# ledrgbmatrix_arjun_with10mil_clearence.net
KiCad netlist of a schematic drawn in EAGLE
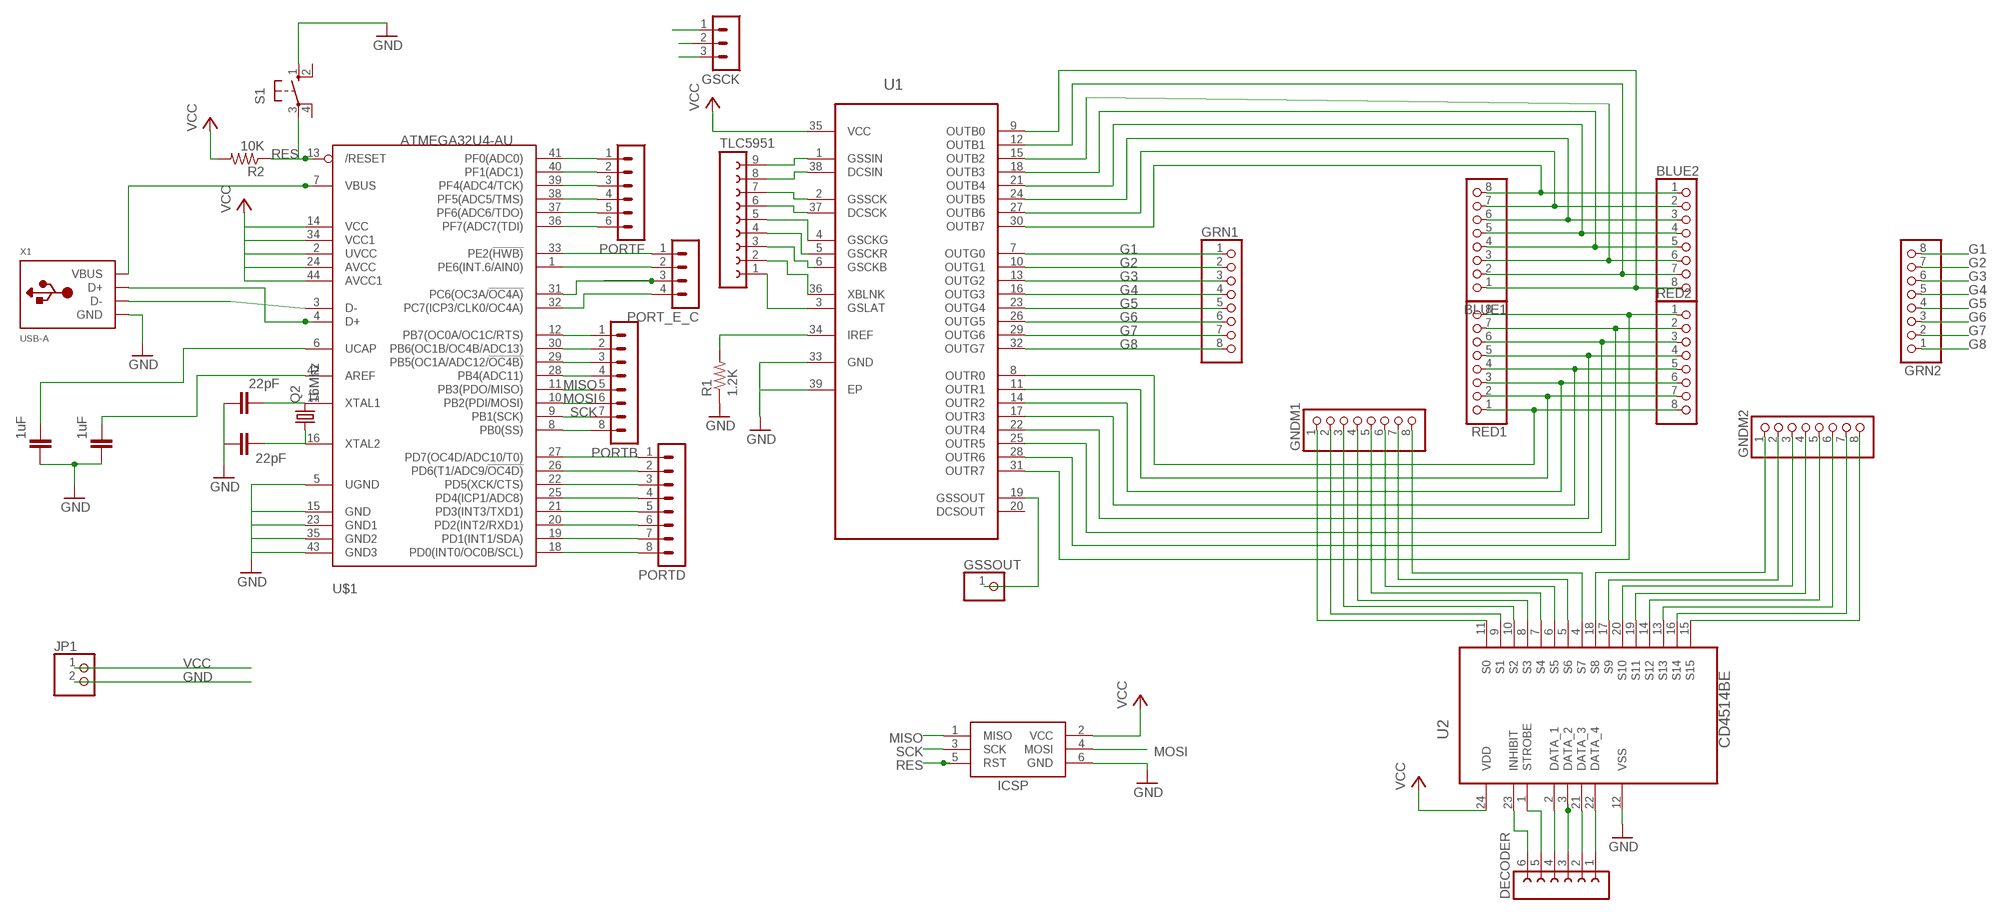
[diagram p0: schematic, sheet 1]

(export (version "E")
  (design (tool "Eeschema 10.0.6"))
  (components
    (comp (ref "BLUE1")
      (value "PINHD-1X8BIG")
      (footprint "eagle-import:1X08-BIG")
      (libsource (lib "eagle-import") (part "PINHD-1X8BIG"))
    )
    (comp (ref "BLUE2")
      (value "PINHD-1X8BIG")
      (footprint "eagle-import:1X08-BIG")
      (libsource (lib "eagle-import") (part "PINHD-1X8BIG"))
    )
    (comp (ref "C1")
      (value "1uF")
      (footprint "eagle-import:C2.5-2")
      (libsource (lib "eagle-import") (part "C2.5/2"))
    )
    (comp (ref "C2")
      (value "1uF")
      (footprint "eagle-import:C2.5-2")
      (libsource (lib "eagle-import") (part "C2.5/2"))
    )
    (comp (ref "C3")
      (value "22pF")
      (footprint "eagle-import:C2.5-2")
      (libsource (lib "eagle-import") (part "C2.5/2"))
    )
    (comp (ref "C4")
      (value "22pF")
      (footprint "eagle-import:C2.5-2")
      (libsource (lib "eagle-import") (part "C2.5/2"))
    )
    (comp (ref "DECODER")
      (value "FE06-1")
      (footprint "eagle-import:FE06")
      (libsource (lib "eagle-import") (part "FE06-1"))
    )
    (comp (ref "GNDM1")
      (value "PINHD-1X8BIG")
      (footprint "eagle-import:1X08-BIG")
      (libsource (lib "eagle-import") (part "PINHD-1X8BIG"))
    )
    (comp (ref "GNDM2")
      (value "PINHD-1X8BIG")
      (footprint "eagle-import:1X08-BIG")
      (libsource (lib "eagle-import") (part "PINHD-1X8BIG"))
    )
    (comp (ref "GRN1")
      (value "PINHD-1X8BIG")
      (footprint "eagle-import:1X08-BIG")
      (libsource (lib "eagle-import") (part "PINHD-1X8BIG"))
    )
    (comp (ref "GRN2")
      (value "PINHD-1X8BIG")
      (footprint "eagle-import:1X08-BIG")
      (libsource (lib "eagle-import") (part "PINHD-1X8BIG"))
    )
    (comp (ref "GSCK")
      (value "MA03-1")
      (footprint "eagle-import:MA03-1")
      (libsource (lib "eagle-import") (part "MA03-1"))
    )
    (comp (ref "GSSOUT")
      (value "PINHD-1X1")
      (footprint "eagle-import:1X01")
      (libsource (lib "eagle-import") (part "PINHD-1X1"))
    )
    (comp (ref "ICSP")
      (value "AVRISP-6")
      (footprint "eagle-import:AVRISP")
      (libsource (lib "eagle-import") (part "AVRISP-6"))
    )
    (comp (ref "JP1")
      (value "PINHD-1X2")
      (footprint "eagle-import:1X02")
      (libsource (lib "eagle-import") (part "PINHD-1X2"))
    )
    (comp (ref "PORTB")
      (value "MA08-1")
      (footprint "eagle-import:MA08-1")
      (libsource (lib "eagle-import") (part "MA08-1"))
    )
    (comp (ref "PORTD")
      (value "MA08-1")
      (footprint "eagle-import:MA08-1")
      (libsource (lib "eagle-import") (part "MA08-1"))
    )
    (comp (ref "PORTF")
      (value "MA06-1")
      (footprint "eagle-import:MA06-1")
      (libsource (lib "eagle-import") (part "MA06-1"))
    )
    (comp (ref "PORT_E_C")
      (value "MA04-1")
      (footprint "eagle-import:MA04-1")
      (libsource (lib "eagle-import") (part "MA04-1"))
    )
    (comp (ref "Q2")
      (value "16Mhz")
      (footprint "eagle-import:HC49U-V")
      (libsource (lib "eagle-import") (part "CRYSTALHC49U-V"))
    )
    (comp (ref "R1")
      (value "1.2K")
      (footprint "eagle-import:0207_12")
      (libsource (lib "eagle-import") (part "R-US_0207/12"))
    )
    (comp (ref "R2")
      (value "10K")
      (footprint "eagle-import:0207_12")
      (libsource (lib "eagle-import") (part "R-US_0207/12"))
    )
    (comp (ref "RED1")
      (value "PINHD-1X8BIG")
      (footprint "eagle-import:1X08-BIG")
      (libsource (lib "eagle-import") (part "PINHD-1X8BIG"))
    )
    (comp (ref "RED2")
      (value "PINHD-1X8BIG")
      (footprint "eagle-import:1X08-BIG")
      (libsource (lib "eagle-import") (part "PINHD-1X8BIG"))
    )
    (comp (ref "S1")
      (value "10-XX")
      (footprint "eagle-import:B3F-10XX")
      (fields (field (name "MPN") "B3F-1000"))
      (libsource (lib "eagle-import") (part "10-XX"))
    )
    (comp (ref "TLC5951")
      (value "FE09-1")
      (footprint "eagle-import:FE09")
      (libsource (lib "eagle-import") (part "FE09-1"))
    )
    (comp (ref "U$1")
      (value "ATMEGA32U4-AU")
      (footprint "eagle-import:TQFP44")
      (libsource (lib "eagle-import") (part "ATMEGA32U4-AU"))
    )
    (comp (ref "U1")
      (value "TLC5951DAP")
      (footprint "eagle-import:SOP65P810X120-39N")
      (libsource (lib "eagle-import") (part "TLC5951DAP"))
    )
    (comp (ref "U2")
      (value "CD4514BE")
      (footprint "eagle-import:DIP254P1080X508-24")
      (libsource (lib "eagle-import") (part "CD4514BE"))
    )
    (comp (ref "X1")
      (value "USB-A")
      (footprint "eagle-import:MOLEX_480371000")
      (libsource (lib "eagle-import") (part "USB-A"))
    )
  )
  (nets
    (net (code "1") (name "/G1") (class "Default")
      (node (ref "GRN1") (pin "1") (pinfunction "1_1") (pintype "passive"))
      (node (ref "GRN2") (pin "8") (pinfunction "8_8") (pintype "passive"))
      (node (ref "U1") (pin "7") (pinfunction "OUTG0_7") (pintype "output"))
    )
    (net (code "2") (name "/G2") (class "Default")
      (node (ref "GRN1") (pin "2") (pinfunction "2_2") (pintype "passive"))
      (node (ref "GRN2") (pin "7") (pinfunction "7_7") (pintype "passive"))
      (node (ref "U1") (pin "10") (pinfunction "OUTG1_10") (pintype "output"))
    )
    (net (code "3") (name "/G3") (class "Default")
      (node (ref "GRN1") (pin "3") (pinfunction "3_3") (pintype "passive"))
      (node (ref "GRN2") (pin "6") (pinfunction "6_6") (pintype "passive"))
      (node (ref "U1") (pin "13") (pinfunction "OUTG2_13") (pintype "output"))
    )
    (net (code "4") (name "/G4") (class "Default")
      (node (ref "GRN1") (pin "4") (pinfunction "4_4") (pintype "passive"))
      (node (ref "GRN2") (pin "5") (pinfunction "5_5") (pintype "passive"))
      (node (ref "U1") (pin "16") (pinfunction "OUTG3_16") (pintype "output"))
    )
    (net (code "5") (name "/G5") (class "Default")
      (node (ref "GRN1") (pin "5") (pinfunction "5_5") (pintype "passive"))
      (node (ref "GRN2") (pin "4") (pinfunction "4_4") (pintype "passive"))
      (node (ref "U1") (pin "23") (pinfunction "OUTG4_23") (pintype "output"))
    )
    (net (code "6") (name "/G6") (class "Default")
      (node (ref "GRN1") (pin "6") (pinfunction "6_6") (pintype "passive"))
      (node (ref "GRN2") (pin "3") (pinfunction "3_3") (pintype "passive"))
      (node (ref "U1") (pin "26") (pinfunction "OUTG5_26") (pintype "output"))
    )
    (net (code "7") (name "/G7") (class "Default")
      (node (ref "GRN1") (pin "7") (pinfunction "7_7") (pintype "passive"))
      (node (ref "GRN2") (pin "2") (pinfunction "2_2") (pintype "passive"))
      (node (ref "U1") (pin "29") (pinfunction "OUTG6_29") (pintype "output"))
    )
    (net (code "8") (name "/G8") (class "Default")
      (node (ref "GRN1") (pin "8") (pinfunction "8_8") (pintype "passive"))
      (node (ref "GRN2") (pin "1") (pinfunction "1_1") (pintype "passive"))
      (node (ref "U1") (pin "32") (pinfunction "OUTG7_32") (pintype "output"))
    )
    (net (code "9") (name "/GSSCK") (class "Default")
      (node (ref "GSCK") (pin "2") (pinfunction "2_2") (pintype "passive"))
      (node (ref "TLC5951") (pin "7") (pinfunction "7_7") (pintype "passive"))
      (node (ref "U1") (pin "2") (pinfunction "GSSCK_2") (pintype "input"))
    )
    (net (code "10") (name "/MISO") (class "Default")
      (node (ref "ICSP") (pin "1") (pinfunction "MISO_1") (pintype "input"))
      (node (ref "PORTB") (pin "5") (pinfunction "5_5") (pintype "passive"))
      (node (ref "U$1") (pin "11") (pinfunction "PB3(PDO/MISO)_11") (pintype "bidirectional"))
    )
    (net (code "11") (name "/MOSI") (class "Default")
      (node (ref "ICSP") (pin "4") (pinfunction "MOSI_4") (pintype "output"))
      (node (ref "PORTB") (pin "6") (pinfunction "6_6") (pintype "passive"))
      (node (ref "U$1") (pin "10") (pinfunction "PB2(PDI/MOSI)_10") (pintype "bidirectional"))
    )
    (net (code "12") (name "/RES") (class "Default")
      (node (ref "ICSP") (pin "5") (pinfunction "RST_5") (pintype "output"))
      (node (ref "R2") (pin "1") (pinfunction "1_1") (pintype "passive"))
      (node (ref "S1") (pin "3") (pinfunction "P_3") (pintype "passive"))
      (node (ref "U$1") (pin "13") (pinfunction "/RESET_13") (pintype "bidirectional"))
    )
    (net (code "13") (name "/SCK") (class "Default")
      (node (ref "ICSP") (pin "3") (pinfunction "SCK_3") (pintype "output"))
      (node (ref "PORTB") (pin "7") (pinfunction "7_7") (pintype "passive"))
      (node (ref "U$1") (pin "9") (pinfunction "PB1(SCK)_9") (pintype "bidirectional"))
    )
    (net (code "14") (name "GND") (class "Default")
      (node (ref "C1") (pin "1") (pinfunction "1_1") (pintype "passive"))
      (node (ref "C2") (pin "1") (pinfunction "1_1") (pintype "passive"))
      (node (ref "C3") (pin "1") (pinfunction "1_1") (pintype "passive"))
      (node (ref "C4") (pin "1") (pinfunction "1_1") (pintype "passive"))
      (node (ref "ICSP") (pin "6") (pinfunction "GND_6") (pintype "power_in"))
      (node (ref "JP1") (pin "2") (pinfunction "2_2") (pintype "passive"))
      (node (ref "R1") (pin "1") (pinfunction "1_1") (pintype "passive"))
      (node (ref "S1") (pin "1") (pinfunction "S_1") (pintype "passive"))
      (node (ref "U$1") (pin "15") (pinfunction "GND_15") (pintype "bidirectional"))
      (node (ref "U$1") (pin "23") (pinfunction "GND1_23") (pintype "bidirectional"))
      (node (ref "U$1") (pin "35") (pinfunction "GND2_35") (pintype "bidirectional"))
      (node (ref "U$1") (pin "43") (pinfunction "GND3_43") (pintype "bidirectional"))
      (node (ref "U$1") (pin "5") (pinfunction "UGND_5") (pintype "bidirectional"))
      (node (ref "U1") (pin "33") (pinfunction "GND_33") (pintype "passive"))
      (node (ref "U1") (pin "39") (pinfunction "EP_39") (pintype "passive"))
      (node (ref "U2") (pin "12") (pinfunction "VSS_12") (pintype "power_in"))
      (node (ref "X1") (pin "4") (pinfunction "GND_4") (pintype "power_in"))
    )
    (net (code "15") (name "Net-(U$1-AREF)") (class "Default")
      (node (ref "C1") (pin "2") (pinfunction "2_2") (pintype "passive"))
      (node (ref "U$1") (pin "42") (pinfunction "AREF_42") (pintype "bidirectional"))
    )
    (net (code "16") (name "Net-(U$1-D+)") (class "Default")
      (node (ref "U$1") (pin "4") (pinfunction "D+_4") (pintype "bidirectional"))
      (node (ref "X1") (pin "3") (pinfunction "D+_3") (pintype "bidirectional"))
    )
    (net (code "17") (name "Net-(U$1-D-)") (class "Default")
      (node (ref "U$1") (pin "3") (pinfunction "D-_3") (pintype "bidirectional"))
      (node (ref "X1") (pin "2") (pinfunction "D-_2") (pintype "bidirectional"))
    )
    (net (code "18") (name "Net-(U$1-PB0(SS))") (class "Default")
      (node (ref "PORTB") (pin "8") (pinfunction "8_8") (pintype "passive"))
      (node (ref "U$1") (pin "8") (pinfunction "PB0(SS)_8") (pintype "bidirectional"))
    )
    (net (code "19") (name "Net-(U$1-PB4(ADC11))") (class "Default")
      (node (ref "PORTB") (pin "4") (pinfunction "4_4") (pintype "passive"))
      (node (ref "U$1") (pin "28") (pinfunction "PB4(ADC11)_28") (pintype "bidirectional"))
    )
    (net (code "20") (name "Net-(U$1-PB5(OC1A{slash}ADC12{slash}~{OC4B}))") (class "Default")
      (node (ref "PORTB") (pin "3") (pinfunction "3_3") (pintype "passive"))
      (node (ref "U$1") (pin "29") (pinfunction "PB5(OC1A/ADC12/~{OC4B})_29") (pintype "bidirectional"))
    )
    (net (code "21") (name "Net-(U$1-PB6(OC1B{slash}OC4B{slash}ADC13))") (class "Default")
      (node (ref "PORTB") (pin "2") (pinfunction "2_2") (pintype "passive"))
      (node (ref "U$1") (pin "30") (pinfunction "PB6(OC1B/OC4B/ADC13)_30") (pintype "bidirectional"))
    )
    (net (code "22") (name "Net-(U$1-PB7(OC0A{slash}OC1C{slash}RTS))") (class "Default")
      (node (ref "PORTB") (pin "1") (pinfunction "1_1") (pintype "passive"))
      (node (ref "U$1") (pin "12") (pinfunction "PB7(OC0A/OC1C/RTS)_12") (pintype "bidirectional"))
    )
    (net (code "23") (name "Net-(U$1-PC6(OC3A{slash}~{OC4A}))") (class "Default")
      (node (ref "PORT_E_C") (pin "3") (pinfunction "3_3") (pintype "passive"))
      (node (ref "U$1") (pin "31") (pinfunction "PC6(OC3A/~{OC4A})_31") (pintype "bidirectional"))
    )
    (net (code "24") (name "Net-(U$1-PC7(ICP3{slash}CLK0{slash}OC4A))") (class "Default")
      (node (ref "PORT_E_C") (pin "4") (pinfunction "4_4") (pintype "passive"))
      (node (ref "U$1") (pin "32") (pinfunction "PC7(ICP3/CLK0/OC4A)_32") (pintype "bidirectional"))
    )
    (net (code "25") (name "Net-(U$1-PD0(INT0{slash}OC0B{slash}SCL))") (class "Default")
      (node (ref "PORTD") (pin "8") (pinfunction "8_8") (pintype "passive"))
      (node (ref "U$1") (pin "18") (pinfunction "PD0(INT0/OC0B/SCL)_18") (pintype "bidirectional"))
    )
    (net (code "26") (name "Net-(U$1-PD1(INT1{slash}SDA))") (class "Default")
      (node (ref "PORTD") (pin "7") (pinfunction "7_7") (pintype "passive"))
      (node (ref "U$1") (pin "19") (pinfunction "PD1(INT1/SDA)_19") (pintype "bidirectional"))
    )
    (net (code "27") (name "Net-(U$1-PD2(INT2{slash}RXD1))") (class "Default")
      (node (ref "PORTD") (pin "6") (pinfunction "6_6") (pintype "passive"))
      (node (ref "U$1") (pin "20") (pinfunction "PD2(INT2/RXD1)_20") (pintype "bidirectional"))
    )
    (net (code "28") (name "Net-(U$1-PD3(INT3{slash}TXD1))") (class "Default")
      (node (ref "PORTD") (pin "5") (pinfunction "5_5") (pintype "passive"))
      (node (ref "U$1") (pin "21") (pinfunction "PD3(INT3/TXD1)_21") (pintype "bidirectional"))
    )
    (net (code "29") (name "Net-(U$1-PD4(ICP1{slash}ADC8))") (class "Default")
      (node (ref "PORTD") (pin "4") (pinfunction "4_4") (pintype "passive"))
      (node (ref "U$1") (pin "25") (pinfunction "PD4(ICP1/ADC8)_25") (pintype "bidirectional"))
    )
    (net (code "30") (name "Net-(U$1-PD5(XCK{slash}CTS))") (class "Default")
      (node (ref "PORTD") (pin "3") (pinfunction "3_3") (pintype "passive"))
      (node (ref "U$1") (pin "22") (pinfunction "PD5(XCK/CTS)_22") (pintype "bidirectional"))
    )
    (net (code "31") (name "Net-(U$1-PD6(T1{slash}ADC9{slash}~{OC4D}))") (class "Default")
      (node (ref "PORTD") (pin "2") (pinfunction "2_2") (pintype "passive"))
      (node (ref "U$1") (pin "26") (pinfunction "PD6(T1/ADC9/~{OC4D})_26") (pintype "bidirectional"))
    )
    (net (code "32") (name "Net-(U$1-PD7(OC4D{slash}ADC10{slash}T0))") (class "Default")
      (node (ref "PORTD") (pin "1") (pinfunction "1_1") (pintype "passive"))
      (node (ref "U$1") (pin "27") (pinfunction "PD7(OC4D/ADC10/T0)_27") (pintype "bidirectional"))
    )
    (net (code "33") (name "Net-(U$1-PE2(~{HWB}))") (class "Default")
      (node (ref "PORT_E_C") (pin "1") (pinfunction "1_1") (pintype "passive"))
      (node (ref "U$1") (pin "33") (pinfunction "PE2(~{HWB})_33") (pintype "bidirectional"))
    )
    (net (code "34") (name "Net-(U$1-PE6(INT.6{slash}AIN0))") (class "Default")
      (node (ref "PORT_E_C") (pin "2") (pinfunction "2_2") (pintype "passive"))
      (node (ref "U$1") (pin "1") (pinfunction "PE6(INT.6/AIN0)_1") (pintype "bidirectional"))
    )
    (net (code "35") (name "Net-(U$1-PF0(ADC0))") (class "Default")
      (node (ref "PORTF") (pin "1") (pinfunction "1_1") (pintype "passive"))
      (node (ref "U$1") (pin "41") (pinfunction "PF0(ADC0)_41") (pintype "bidirectional"))
    )
    (net (code "36") (name "Net-(U$1-PF1(ADC1))") (class "Default")
      (node (ref "PORTF") (pin "2") (pinfunction "2_2") (pintype "passive"))
      (node (ref "U$1") (pin "40") (pinfunction "PF1(ADC1)_40") (pintype "bidirectional"))
    )
    (net (code "37") (name "Net-(U$1-PF4(ADC4{slash}TCK))") (class "Default")
      (node (ref "PORTF") (pin "3") (pinfunction "3_3") (pintype "passive"))
      (node (ref "U$1") (pin "39") (pinfunction "PF4(ADC4/TCK)_39") (pintype "bidirectional"))
    )
    (net (code "38") (name "Net-(U$1-PF5(ADC5{slash}TMS))") (class "Default")
      (node (ref "PORTF") (pin "4") (pinfunction "4_4") (pintype "passive"))
      (node (ref "U$1") (pin "38") (pinfunction "PF5(ADC5/TMS)_38") (pintype "bidirectional"))
    )
    (net (code "39") (name "Net-(U$1-PF6(ADC6{slash}TDO))") (class "Default")
      (node (ref "PORTF") (pin "5") (pinfunction "5_5") (pintype "passive"))
      (node (ref "U$1") (pin "37") (pinfunction "PF6(ADC6/TDO)_37") (pintype "bidirectional"))
    )
    (net (code "40") (name "Net-(U$1-PF7(ADC7(TDI))") (class "Default")
      (node (ref "PORTF") (pin "6") (pinfunction "6_6") (pintype "passive"))
      (node (ref "U$1") (pin "36") (pinfunction "PF7(ADC7(TDI)_36") (pintype "bidirectional"))
    )
    (net (code "41") (name "Net-(U$1-UCAP)") (class "Default")
      (node (ref "C2") (pin "2") (pinfunction "2_2") (pintype "passive"))
      (node (ref "U$1") (pin "6") (pinfunction "UCAP_6") (pintype "bidirectional"))
    )
    (net (code "42") (name "Net-(U$1-VBUS)") (class "Default")
      (node (ref "U$1") (pin "7") (pinfunction "VBUS_7") (pintype "bidirectional"))
      (node (ref "X1") (pin "1") (pinfunction "VBUS_1") (pintype "power_in"))
    )
    (net (code "43") (name "Net-(U$1-XTAL1)") (class "Default")
      (node (ref "C3") (pin "2") (pinfunction "2_2") (pintype "passive"))
      (node (ref "Q2") (pin "2") (pinfunction "2_2") (pintype "passive"))
      (node (ref "U$1") (pin "17") (pinfunction "XTAL1_17") (pintype "bidirectional"))
    )
    (net (code "44") (name "Net-(U$1-XTAL2)") (class "Default")
      (node (ref "C4") (pin "2") (pinfunction "2_2") (pintype "passive"))
      (node (ref "Q2") (pin "1") (pinfunction "1_1") (pintype "passive"))
      (node (ref "U$1") (pin "16") (pinfunction "XTAL2_16") (pintype "bidirectional"))
    )
    (net (code "45") (name "Net-(U1-DCSCK)") (class "Default")
      (node (ref "TLC5951") (pin "6") (pinfunction "6_6") (pintype "passive"))
      (node (ref "U1") (pin "37") (pinfunction "DCSCK_37") (pintype "input"))
    )
    (net (code "46") (name "Net-(U1-DCSIN)") (class "Default")
      (node (ref "TLC5951") (pin "8") (pinfunction "8_8") (pintype "passive"))
      (node (ref "U1") (pin "38") (pinfunction "DCSIN_38") (pintype "input"))
    )
    (net (code "47") (name "Net-(U1-GSCKB)") (class "Default")
      (node (ref "TLC5951") (pin "3") (pinfunction "3_3") (pintype "passive"))
      (node (ref "U1") (pin "6") (pinfunction "GSCKB_6") (pintype "input"))
    )
    (net (code "48") (name "Net-(U1-GSCKG)") (class "Default")
      (node (ref "TLC5951") (pin "5") (pinfunction "5_5") (pintype "passive"))
      (node (ref "U1") (pin "4") (pinfunction "GSCKG_4") (pintype "input"))
    )
    (net (code "49") (name "Net-(U1-GSCKR)") (class "Default")
      (node (ref "TLC5951") (pin "4") (pinfunction "4_4") (pintype "passive"))
      (node (ref "U1") (pin "5") (pinfunction "GSCKR_5") (pintype "input"))
    )
    (net (code "50") (name "Net-(U1-GSLAT)") (class "Default")
      (node (ref "TLC5951") (pin "1") (pinfunction "1_1") (pintype "passive"))
      (node (ref "U1") (pin "3") (pinfunction "GSLAT_3") (pintype "input"))
    )
    (net (code "51") (name "Net-(U1-GSSIN)") (class "Default")
      (node (ref "TLC5951") (pin "9") (pinfunction "9_9") (pintype "passive"))
      (node (ref "U1") (pin "1") (pinfunction "GSSIN_1") (pintype "input"))
    )
    (net (code "52") (name "Net-(U1-GSSOUT)") (class "Default")
      (node (ref "GSSOUT") (pin "1") (pinfunction "1_1") (pintype "passive"))
      (node (ref "U1") (pin "19") (pinfunction "GSSOUT_19") (pintype "output"))
    )
    (net (code "53") (name "Net-(U1-IREF)") (class "Default")
      (node (ref "R1") (pin "2") (pinfunction "2_2") (pintype "passive"))
      (node (ref "U1") (pin "34") (pinfunction "IREF_34") (pintype "bidirectional"))
    )
    (net (code "54") (name "Net-(U1-OUTB0)") (class "Default")
      (node (ref "BLUE1") (pin "1") (pinfunction "1_1") (pintype "passive"))
      (node (ref "BLUE2") (pin "8") (pinfunction "8_8") (pintype "passive"))
      (node (ref "U1") (pin "9") (pinfunction "OUTB0_9") (pintype "output"))
    )
    (net (code "55") (name "Net-(U1-OUTB1)") (class "Default")
      (node (ref "BLUE1") (pin "2") (pinfunction "2_2") (pintype "passive"))
      (node (ref "BLUE2") (pin "7") (pinfunction "7_7") (pintype "passive"))
      (node (ref "U1") (pin "12") (pinfunction "OUTB1_12") (pintype "output"))
    )
    (net (code "56") (name "Net-(U1-OUTB2)") (class "Default")
      (node (ref "BLUE1") (pin "3") (pinfunction "3_3") (pintype "passive"))
      (node (ref "BLUE2") (pin "6") (pinfunction "6_6") (pintype "passive"))
      (node (ref "U1") (pin "15") (pinfunction "OUTB2_15") (pintype "output"))
    )
    (net (code "57") (name "Net-(U1-OUTB3)") (class "Default")
      (node (ref "BLUE1") (pin "4") (pinfunction "4_4") (pintype "passive"))
      (node (ref "BLUE2") (pin "5") (pinfunction "5_5") (pintype "passive"))
      (node (ref "U1") (pin "18") (pinfunction "OUTB3_18") (pintype "output"))
    )
    (net (code "58") (name "Net-(U1-OUTB4)") (class "Default")
      (node (ref "BLUE1") (pin "5") (pinfunction "5_5") (pintype "passive"))
      (node (ref "BLUE2") (pin "4") (pinfunction "4_4") (pintype "passive"))
      (node (ref "U1") (pin "21") (pinfunction "OUTB4_21") (pintype "output"))
    )
    (net (code "59") (name "Net-(U1-OUTB5)") (class "Default")
      (node (ref "BLUE1") (pin "6") (pinfunction "6_6") (pintype "passive"))
      (node (ref "BLUE2") (pin "3") (pinfunction "3_3") (pintype "passive"))
      (node (ref "U1") (pin "24") (pinfunction "OUTB5_24") (pintype "output"))
    )
    (net (code "60") (name "Net-(U1-OUTB6)") (class "Default")
      (node (ref "BLUE1") (pin "7") (pinfunction "7_7") (pintype "passive"))
      (node (ref "BLUE2") (pin "2") (pinfunction "2_2") (pintype "passive"))
      (node (ref "U1") (pin "27") (pinfunction "OUTB6_27") (pintype "output"))
    )
    (net (code "61") (name "Net-(U1-OUTB7)") (class "Default")
      (node (ref "BLUE1") (pin "8") (pinfunction "8_8") (pintype "passive"))
      (node (ref "BLUE2") (pin "1") (pinfunction "1_1") (pintype "passive"))
      (node (ref "U1") (pin "30") (pinfunction "OUTB7_30") (pintype "output"))
    )
    (net (code "62") (name "Net-(U1-OUTR0)") (class "Default")
      (node (ref "RED1") (pin "1") (pinfunction "1_1") (pintype "passive"))
      (node (ref "RED2") (pin "8") (pinfunction "8_8") (pintype "passive"))
      (node (ref "U1") (pin "8") (pinfunction "OUTR0_8") (pintype "output"))
    )
    (net (code "63") (name "Net-(U1-OUTR1)") (class "Default")
      (node (ref "RED1") (pin "2") (pinfunction "2_2") (pintype "passive"))
      (node (ref "RED2") (pin "7") (pinfunction "7_7") (pintype "passive"))
      (node (ref "U1") (pin "11") (pinfunction "OUTR1_11") (pintype "output"))
    )
    (net (code "64") (name "Net-(U1-OUTR2)") (class "Default")
      (node (ref "RED1") (pin "3") (pinfunction "3_3") (pintype "passive"))
      (node (ref "RED2") (pin "6") (pinfunction "6_6") (pintype "passive"))
      (node (ref "U1") (pin "14") (pinfunction "OUTR2_14") (pintype "output"))
    )
    (net (code "65") (name "Net-(U1-OUTR3)") (class "Default")
      (node (ref "RED1") (pin "4") (pinfunction "4_4") (pintype "passive"))
      (node (ref "RED2") (pin "5") (pinfunction "5_5") (pintype "passive"))
      (node (ref "U1") (pin "17") (pinfunction "OUTR3_17") (pintype "output"))
    )
    (net (code "66") (name "Net-(U1-OUTR4)") (class "Default")
      (node (ref "RED1") (pin "5") (pinfunction "5_5") (pintype "passive"))
      (node (ref "RED2") (pin "4") (pinfunction "4_4") (pintype "passive"))
      (node (ref "U1") (pin "22") (pinfunction "OUTR4_22") (pintype "output"))
    )
    (net (code "67") (name "Net-(U1-OUTR5)") (class "Default")
      (node (ref "RED1") (pin "6") (pinfunction "6_6") (pintype "passive"))
      (node (ref "RED2") (pin "3") (pinfunction "3_3") (pintype "passive"))
      (node (ref "U1") (pin "25") (pinfunction "OUTR5_25") (pintype "output"))
    )
    (net (code "68") (name "Net-(U1-OUTR6)") (class "Default")
      (node (ref "RED1") (pin "7") (pinfunction "7_7") (pintype "passive"))
      (node (ref "RED2") (pin "2") (pinfunction "2_2") (pintype "passive"))
      (node (ref "U1") (pin "28") (pinfunction "OUTR6_28") (pintype "output"))
    )
    (net (code "69") (name "Net-(U1-OUTR7)") (class "Default")
      (node (ref "RED1") (pin "8") (pinfunction "8_8") (pintype "passive"))
      (node (ref "RED2") (pin "1") (pinfunction "1_1") (pintype "passive"))
      (node (ref "U1") (pin "31") (pinfunction "OUTR7_31") (pintype "output"))
    )
    (net (code "70") (name "Net-(U1-XBLNK)") (class "Default")
      (node (ref "TLC5951") (pin "2") (pinfunction "2_2") (pintype "passive"))
      (node (ref "U1") (pin "36") (pinfunction "XBLNK_36") (pintype "input"))
    )
    (net (code "71") (name "Net-(U2-DATA_1)") (class "Default")
      (node (ref "DECODER") (pin "4") (pinfunction "4_4") (pintype "passive"))
      (node (ref "U2") (pin "2") (pinfunction "DATA_1_2") (pintype "input"))
    )
    (net (code "72") (name "Net-(U2-DATA_2)") (class "Default")
      (node (ref "DECODER") (pin "3") (pinfunction "3_3") (pintype "passive"))
      (node (ref "U2") (pin "3") (pinfunction "DATA_2_3") (pintype "input"))
    )
    (net (code "73") (name "Net-(U2-DATA_3)") (class "Default")
      (node (ref "DECODER") (pin "2") (pinfunction "2_2") (pintype "passive"))
      (node (ref "U2") (pin "21") (pinfunction "DATA_3_21") (pintype "input"))
    )
    (net (code "74") (name "Net-(U2-DATA_4)") (class "Default")
      (node (ref "DECODER") (pin "1") (pinfunction "1_1") (pintype "passive"))
      (node (ref "U2") (pin "22") (pinfunction "DATA_4_22") (pintype "input"))
    )
    (net (code "75") (name "Net-(U2-INHIBIT)") (class "Default")
      (node (ref "DECODER") (pin "6") (pinfunction "6_6") (pintype "passive"))
      (node (ref "U2") (pin "23") (pinfunction "INHIBIT_23") (pintype "input"))
    )
    (net (code "76") (name "Net-(U2-S0)") (class "Default")
      (node (ref "GNDM1") (pin "1") (pinfunction "1_1") (pintype "passive"))
      (node (ref "U2") (pin "11") (pinfunction "S0_11") (pintype "output"))
    )
    (net (code "77") (name "Net-(U2-S1)") (class "Default")
      (node (ref "GNDM1") (pin "2") (pinfunction "2_2") (pintype "passive"))
      (node (ref "U2") (pin "9") (pinfunction "S1_9") (pintype "output"))
    )
    (net (code "78") (name "Net-(U2-S2)") (class "Default")
      (node (ref "GNDM1") (pin "3") (pinfunction "3_3") (pintype "passive"))
      (node (ref "U2") (pin "10") (pinfunction "S2_10") (pintype "output"))
    )
    (net (code "79") (name "Net-(U2-S3)") (class "Default")
      (node (ref "GNDM1") (pin "4") (pinfunction "4_4") (pintype "passive"))
      (node (ref "U2") (pin "8") (pinfunction "S3_8") (pintype "output"))
    )
    (net (code "80") (name "Net-(U2-S4)") (class "Default")
      (node (ref "GNDM1") (pin "5") (pinfunction "5_5") (pintype "passive"))
      (node (ref "U2") (pin "7") (pinfunction "S4_7") (pintype "output"))
    )
    (net (code "81") (name "Net-(U2-S5)") (class "Default")
      (node (ref "GNDM1") (pin "6") (pinfunction "6_6") (pintype "passive"))
      (node (ref "U2") (pin "6") (pinfunction "S5_6") (pintype "output"))
    )
    (net (code "82") (name "Net-(U2-S6)") (class "Default")
      (node (ref "GNDM1") (pin "7") (pinfunction "7_7") (pintype "passive"))
      (node (ref "U2") (pin "5") (pinfunction "S6_5") (pintype "output"))
    )
    (net (code "83") (name "Net-(U2-S7)") (class "Default")
      (node (ref "GNDM1") (pin "8") (pinfunction "8_8") (pintype "passive"))
      (node (ref "U2") (pin "4") (pinfunction "S7_4") (pintype "output"))
    )
    (net (code "84") (name "Net-(U2-S8)") (class "Default")
      (node (ref "GNDM2") (pin "1") (pinfunction "1_1") (pintype "passive"))
      (node (ref "U2") (pin "18") (pinfunction "S8_18") (pintype "output"))
    )
    (net (code "85") (name "Net-(U2-S9)") (class "Default")
      (node (ref "GNDM2") (pin "2") (pinfunction "2_2") (pintype "passive"))
      (node (ref "U2") (pin "17") (pinfunction "S9_17") (pintype "output"))
    )
    (net (code "86") (name "Net-(U2-S10)") (class "Default")
      (node (ref "GNDM2") (pin "3") (pinfunction "3_3") (pintype "passive"))
      (node (ref "U2") (pin "20") (pinfunction "S10_20") (pintype "output"))
    )
    (net (code "87") (name "Net-(U2-S11)") (class "Default")
      (node (ref "GNDM2") (pin "4") (pinfunction "4_4") (pintype "passive"))
      (node (ref "U2") (pin "19") (pinfunction "S11_19") (pintype "output"))
    )
    (net (code "88") (name "Net-(U2-S12)") (class "Default")
      (node (ref "GNDM2") (pin "5") (pinfunction "5_5") (pintype "passive"))
      (node (ref "U2") (pin "14") (pinfunction "S12_14") (pintype "output"))
    )
    (net (code "89") (name "Net-(U2-S13)") (class "Default")
      (node (ref "GNDM2") (pin "6") (pinfunction "6_6") (pintype "passive"))
      (node (ref "U2") (pin "13") (pinfunction "S13_13") (pintype "output"))
    )
    (net (code "90") (name "Net-(U2-S14)") (class "Default")
      (node (ref "GNDM2") (pin "7") (pinfunction "7_7") (pintype "passive"))
      (node (ref "U2") (pin "16") (pinfunction "S14_16") (pintype "output"))
    )
    (net (code "91") (name "Net-(U2-S15)") (class "Default")
      (node (ref "GNDM2") (pin "8") (pinfunction "8_8") (pintype "passive"))
      (node (ref "U2") (pin "15") (pinfunction "S15_15") (pintype "output"))
    )
    (net (code "92") (name "Net-(U2-STROBE)") (class "Default")
      (node (ref "DECODER") (pin "5") (pinfunction "5_5") (pintype "passive"))
      (node (ref "U2") (pin "1") (pinfunction "STROBE_1") (pintype "input"))
    )
    (net (code "93") (name "VCC") (class "Default")
      (node (ref "ICSP") (pin "2") (pinfunction "VCC_2") (pintype "power_in"))
      (node (ref "JP1") (pin "1") (pinfunction "1_1") (pintype "passive"))
      (node (ref "R2") (pin "2") (pinfunction "2_2") (pintype "passive"))
      (node (ref "U$1") (pin "14") (pinfunction "VCC_14") (pintype "bidirectional"))
      (node (ref "U$1") (pin "2") (pinfunction "UVCC_2") (pintype "bidirectional"))
      (node (ref "U$1") (pin "24") (pinfunction "AVCC_24") (pintype "bidirectional"))
      (node (ref "U$1") (pin "34") (pinfunction "VCC1_34") (pintype "bidirectional"))
      (node (ref "U$1") (pin "44") (pinfunction "AVCC1_44") (pintype "bidirectional"))
      (node (ref "U1") (pin "35") (pinfunction "VCC_35") (pintype "power_in"))
      (node (ref "U2") (pin "24") (pinfunction "VDD_24") (pintype "power_in"))
    )
    (net (code "94") (name "unconnected-(GSCK-Pad1)") (class "Default")
      (node (ref "GSCK") (pin "1") (pinfunction "1_1") (pintype "passive"))
    )
    (net (code "95") (name "unconnected-(GSCK-Pad3)") (class "Default")
      (node (ref "GSCK") (pin "3") (pinfunction "3_3") (pintype "passive"))
    )
    (net (code "96") (name "unconnected-(S1-P1-Pad4)") (class "Default")
      (node (ref "S1") (pin "4") (pinfunction "P1_4") (pintype "passive"))
    )
    (net (code "97") (name "unconnected-(S1-S1-Pad2)") (class "Default")
      (node (ref "S1") (pin "2") (pinfunction "S1_2") (pintype "passive"))
    )
    (net (code "98") (name "unconnected-(U1-DCSOUT-Pad20)") (class "Default")
      (node (ref "U1") (pin "20") (pinfunction "DCSOUT_20") (pintype "output"))
    )
  )
)
